# Multimeter.net
KiCad netlist of a schematic drawn in EAGLE
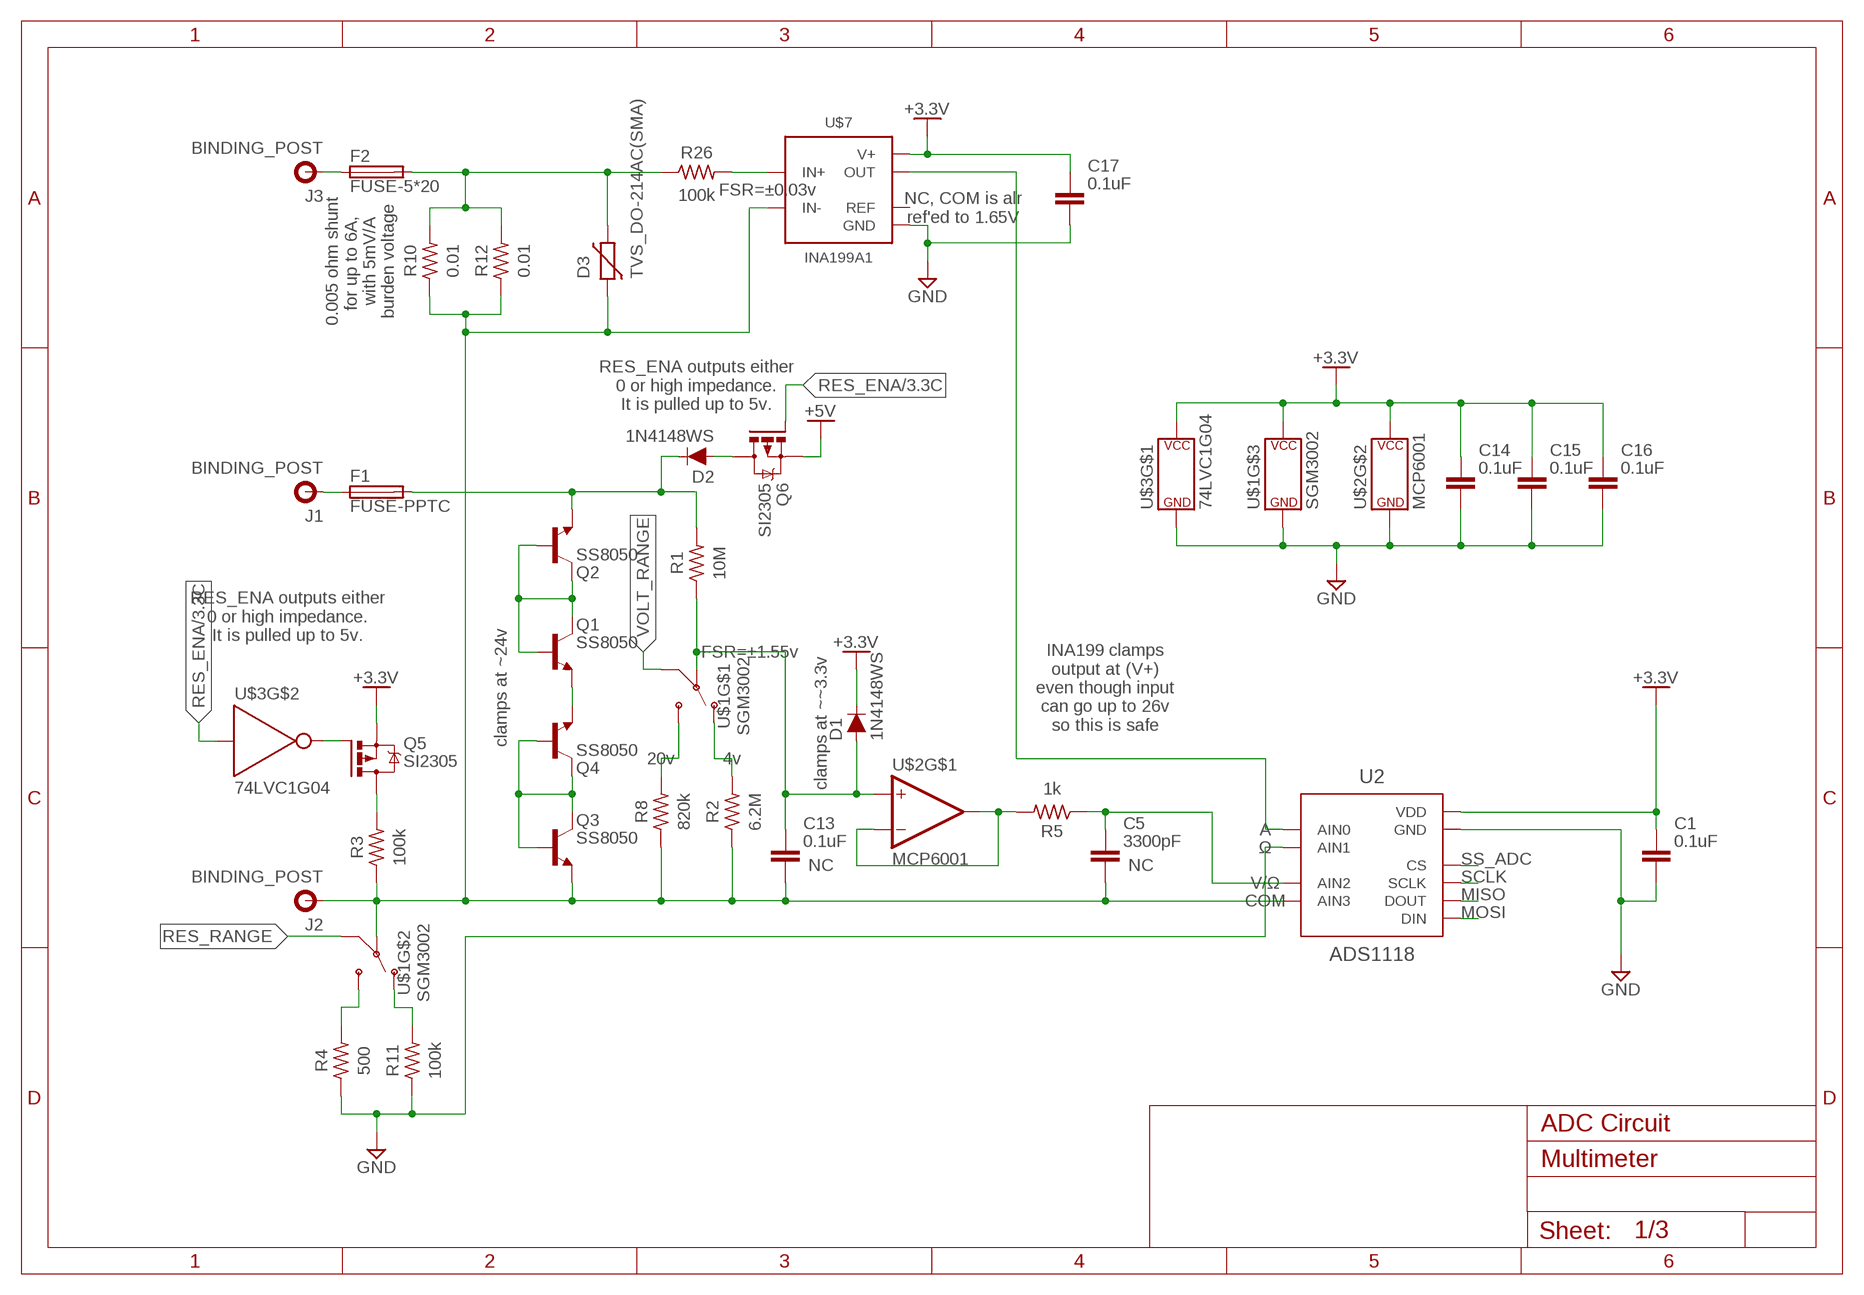
[diagram p0: schematic, sheet 1]
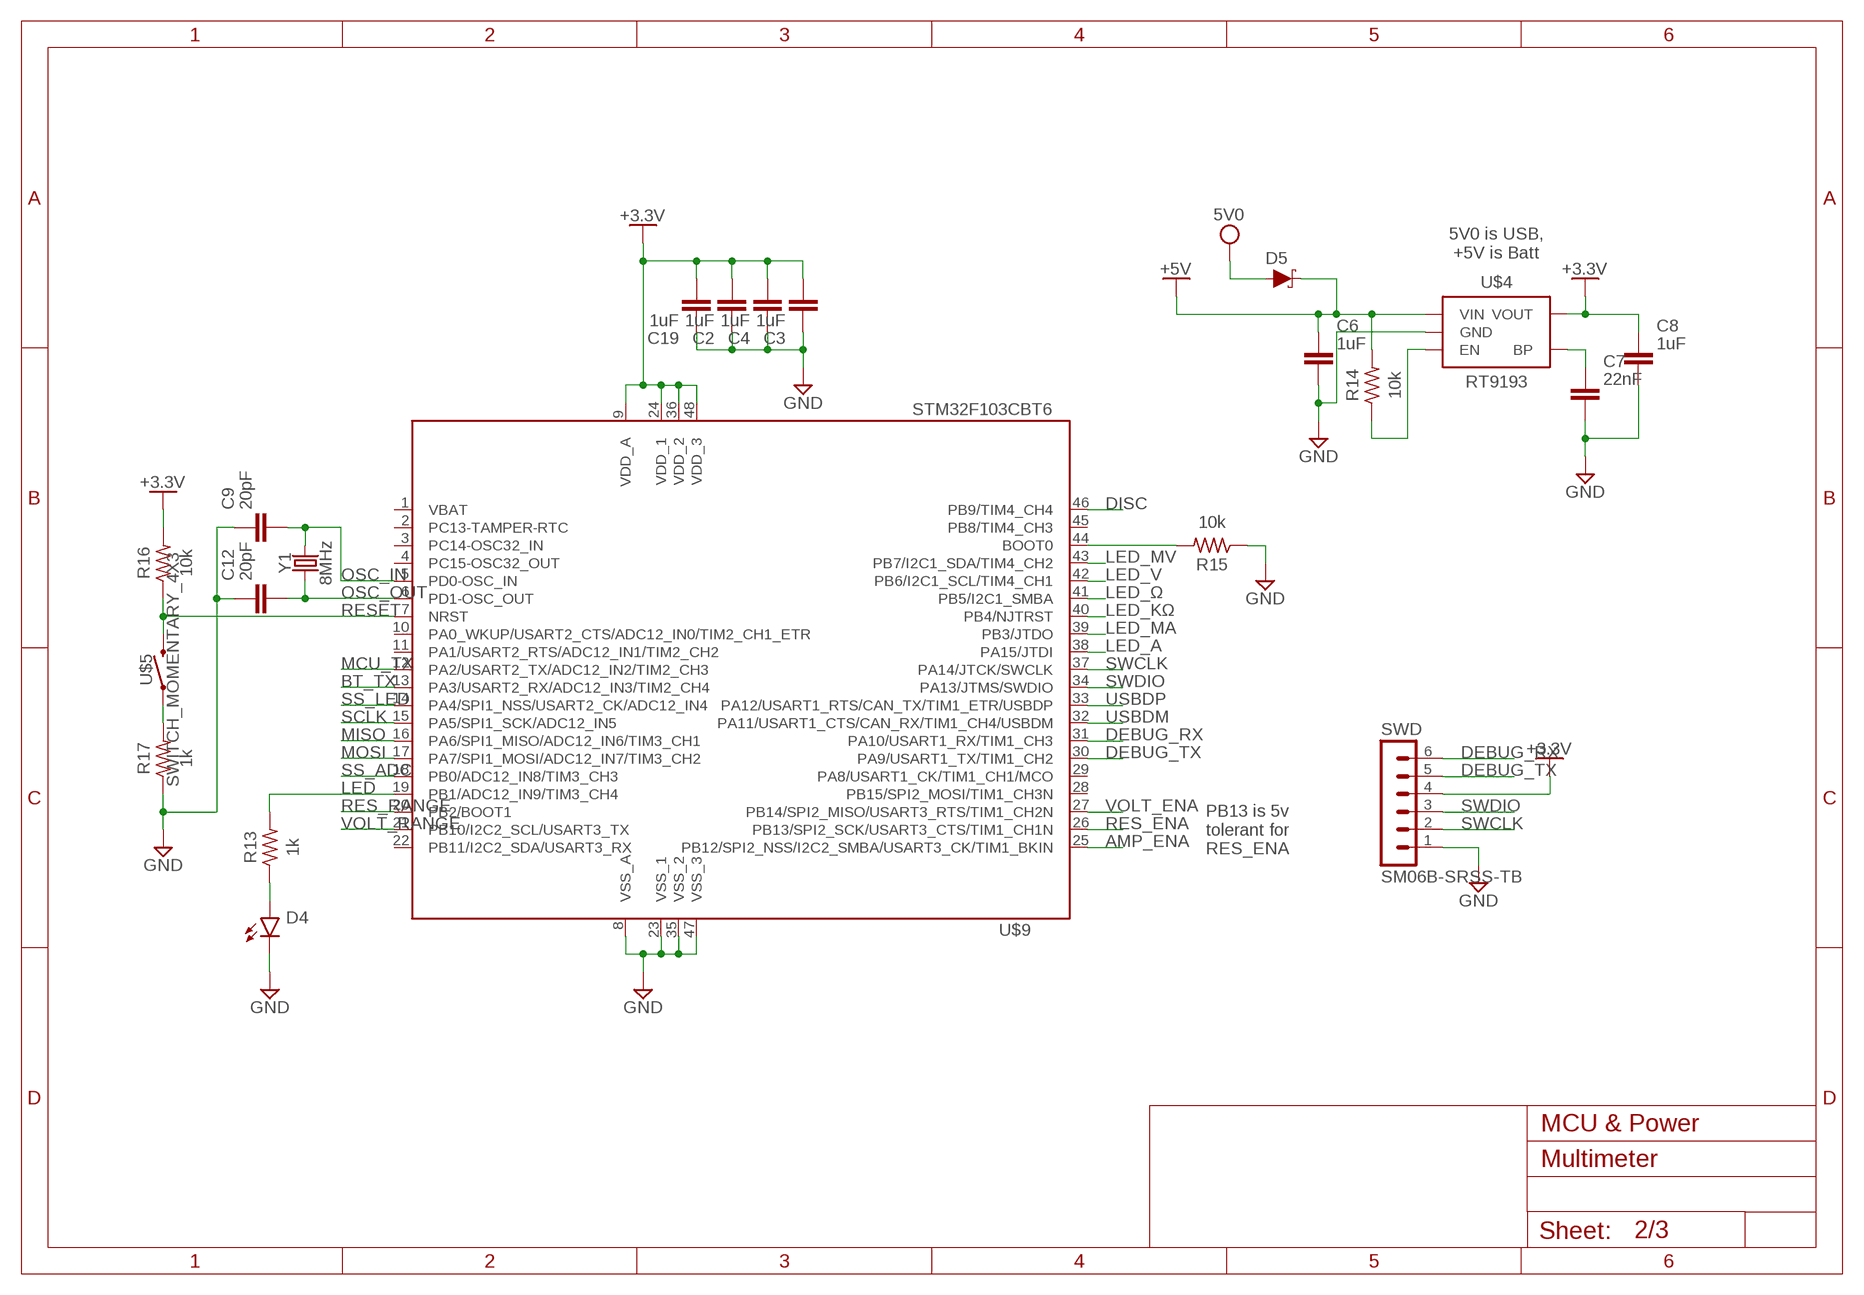
[diagram p1: schematic, sheet 2]
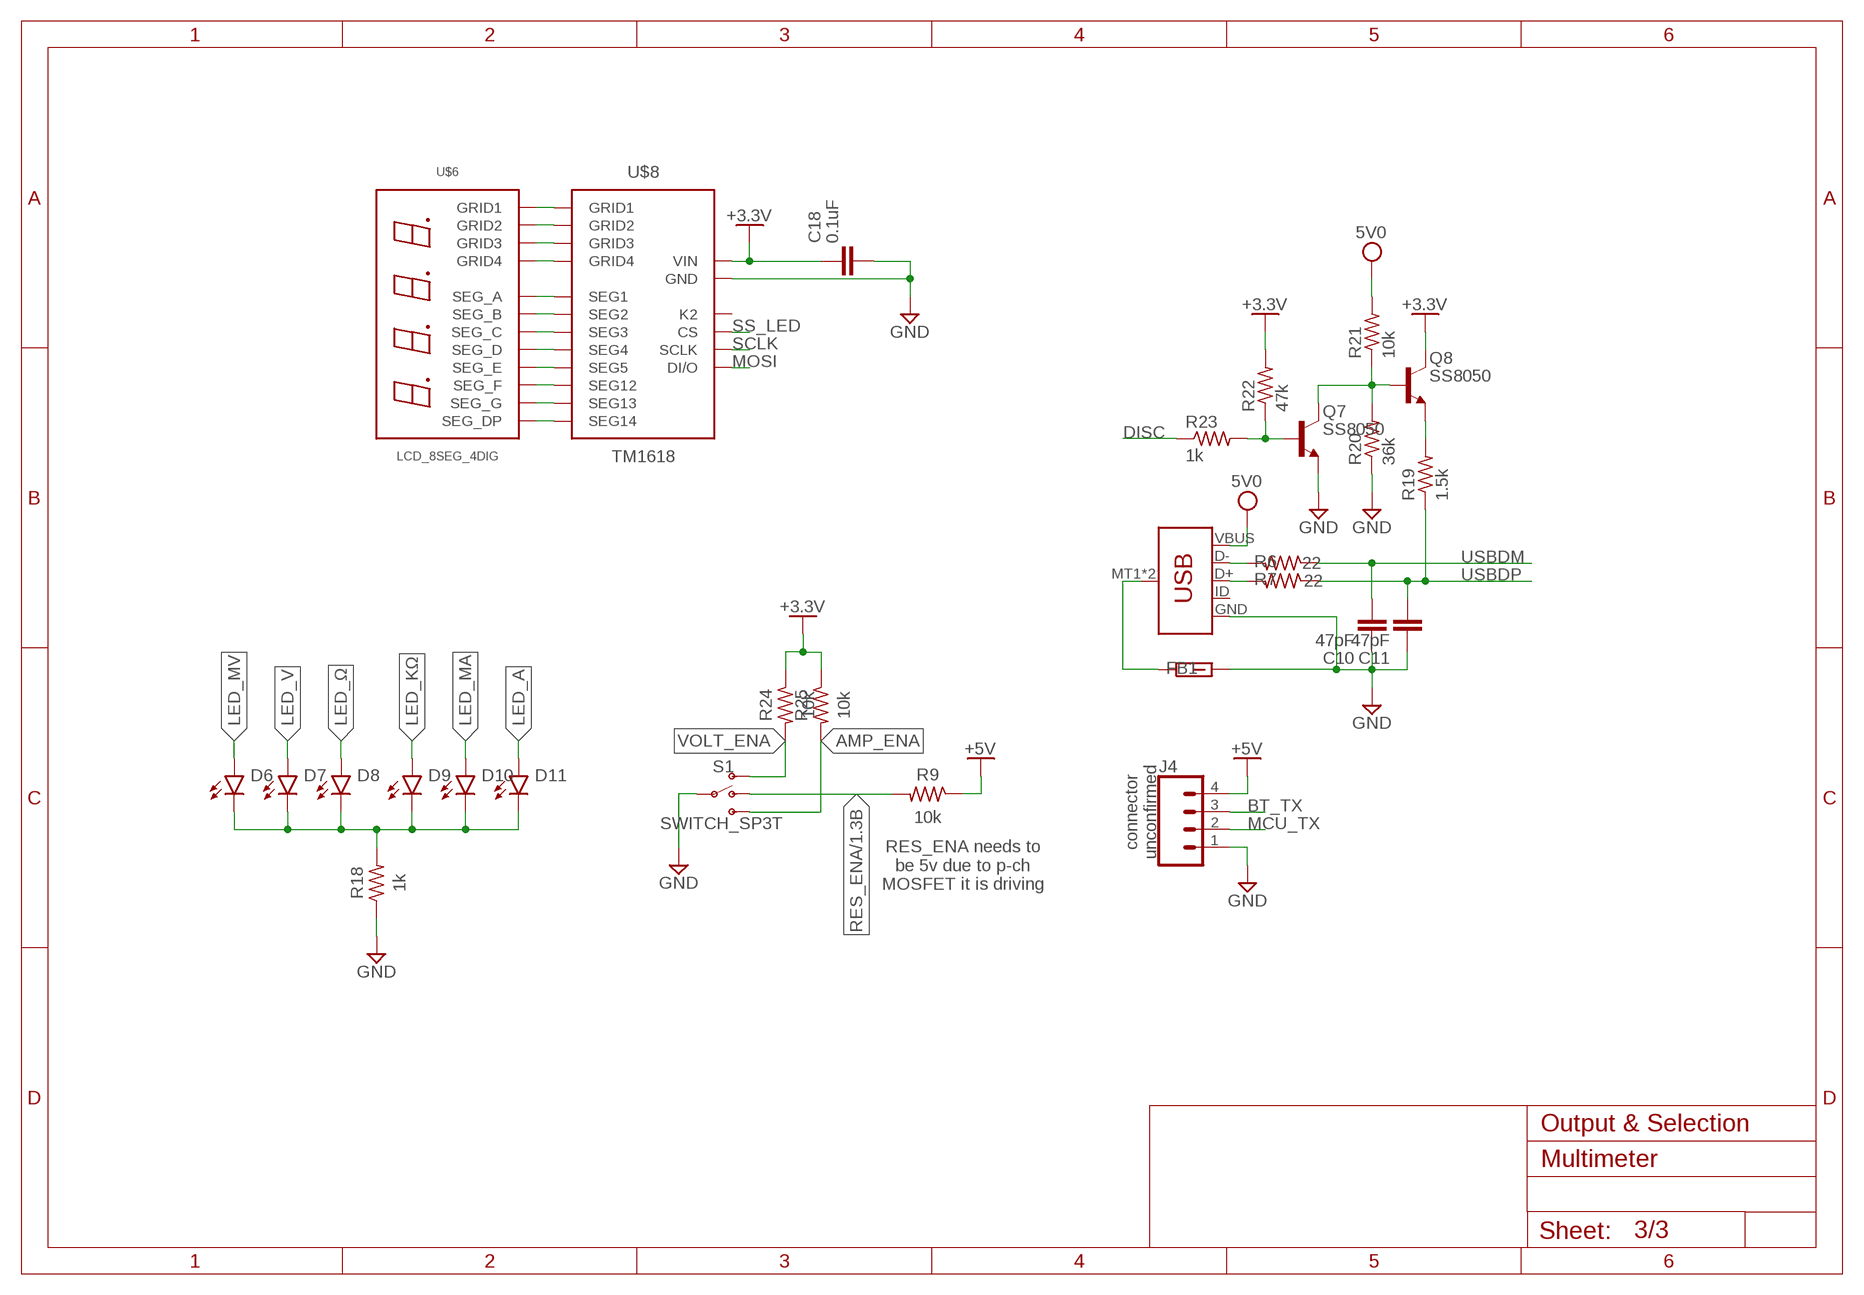
[diagram p2: schematic, sheet 3]

(export (version "E")
  (design (tool "Eeschema 10.0.6"))
  (components
    (comp (ref "C1")
      (value "0.1uF")
      (footprint "eagle-import:CAPC1608X85")
      (libsource (lib "eagle-import") (part "CCHIP-0603(1608-METRIC)_"))
    )
    (comp (ref "C5")
      (value "3300pF")
      (footprint "eagle-import:CAPC1608X85")
      (libsource (lib "eagle-import") (part "CCHIP-0603(1608-METRIC)_"))
    )
    (comp (ref "C13")
      (value "0.1uF")
      (footprint "eagle-import:CAPC1608X85")
      (libsource (lib "eagle-import") (part "CCHIP-0603(1608-METRIC)_"))
    )
    (comp (ref "C14")
      (value "0.1uF")
      (footprint "eagle-import:CAPC1608X85")
      (libsource (lib "eagle-import") (part "CCHIP-0603(1608-METRIC)_"))
    )
    (comp (ref "C15")
      (value "0.1uF")
      (footprint "eagle-import:CAPC1608X85")
      (libsource (lib "eagle-import") (part "CCHIP-0603(1608-METRIC)_"))
    )
    (comp (ref "C16")
      (value "0.1uF")
      (footprint "eagle-import:CAPC1608X85")
      (libsource (lib "eagle-import") (part "CCHIP-0603(1608-METRIC)_"))
    )
    (comp (ref "C17")
      (value "0.1uF")
      (footprint "eagle-import:CAPC1608X85")
      (libsource (lib "eagle-import") (part "CCHIP-0603(1608-METRIC)_"))
    )
    (comp (ref "D1")
      (value "1N4148WS")
      (footprint "eagle-import:SOD-323")
      (libsource (lib "eagle-import") (part "DIODE"))
    )
    (comp (ref "D2")
      (value "1N4148WS")
      (footprint "eagle-import:SOD-323")
      (libsource (lib "eagle-import") (part "DIODE"))
    )
    (comp (ref "D3")
      (value "TVS_DO-214AC(SMA)")
      (footprint "eagle-import:DIOM5226X290N")
      (libsource (lib "eagle-import") (part "TVSDO-214AC(SMA)_"))
    )
    (comp (ref "F1")
      (value "FUSE-PPTC")
      (footprint "eagle-import:FUSE-PPTC-TH")
      (libsource (lib "eagle-import") (part "FUSE-PPTC"))
    )
    (comp (ref "F2")
      (value "FUSE-5*20")
      (footprint "eagle-import:FUSEHOLDER__HD_")
      (libsource (lib "eagle-import") (part "FUSE-520"))
    )
    (comp (ref "J1")
      (value "BINDING_POST")
      (footprint "eagle-import:BINDING_POST")
      (libsource (lib "eagle-import") (part "BINDING_POST"))
    )
    (comp (ref "J2")
      (value "BINDING_POST")
      (footprint "eagle-import:BINDING_POST")
      (libsource (lib "eagle-import") (part "BINDING_POST"))
    )
    (comp (ref "J3")
      (value "BINDING_POST")
      (footprint "eagle-import:BINDING_POST")
      (libsource (lib "eagle-import") (part "BINDING_POST"))
    )
    (comp (ref "Q1")
      (value "SS8050")
      (footprint "eagle-import:SOT95P237X112-3N")
      (libsource (lib "eagle-import") (part "NPNSOT23_"))
    )
    (comp (ref "Q2")
      (value "SS8050")
      (footprint "eagle-import:SOT95P237X112-3N")
      (libsource (lib "eagle-import") (part "NPNSOT23_"))
    )
    (comp (ref "Q3")
      (value "SS8050")
      (footprint "eagle-import:SOT95P237X112-3N")
      (libsource (lib "eagle-import") (part "NPNSOT23_"))
    )
    (comp (ref "Q4")
      (value "SS8050")
      (footprint "eagle-import:SOT95P237X112-3N")
      (libsource (lib "eagle-import") (part "NPNSOT23_"))
    )
    (comp (ref "Q5")
      (value "SI2305")
      (footprint "eagle-import:SOT23")
      (libsource (lib "eagle-import") (part "PMOSFETSOT23_"))
    )
    (comp (ref "Q6")
      (value "SI2305")
      (footprint "eagle-import:SOT23")
      (libsource (lib "eagle-import") (part "PMOSFETSOT23_"))
    )
    (comp (ref "R1")
      (value "10M")
      (footprint "eagle-import:RESC1608X60")
      (libsource (lib "eagle-import") (part "R-USCHIP-0603(1608-METRIC)_"))
    )
    (comp (ref "R2")
      (value "6.2M")
      (footprint "eagle-import:RESC1608X60")
      (libsource (lib "eagle-import") (part "R-USCHIP-0603(1608-METRIC)_"))
    )
    (comp (ref "R3")
      (value "100k")
      (footprint "eagle-import:RESC1608X60")
      (libsource (lib "eagle-import") (part "R-USCHIP-0603(1608-METRIC)_"))
    )
    (comp (ref "R4")
      (value "500")
      (footprint "eagle-import:RESC1608X60")
      (libsource (lib "eagle-import") (part "R-USCHIP-0603(1608-METRIC)_"))
    )
    (comp (ref "R5")
      (value "1k")
      (footprint "eagle-import:RESC1608X60")
      (libsource (lib "eagle-import") (part "R-USCHIP-0603(1608-METRIC)_"))
    )
    (comp (ref "R8")
      (value "820k")
      (footprint "eagle-import:RESC1608X60")
      (libsource (lib "eagle-import") (part "R-USCHIP-0603(1608-METRIC)_"))
    )
    (comp (ref "R10")
      (value "0.01")
      (footprint "eagle-import:RESC6332X71")
      (libsource (lib "eagle-import") (part "R-USCHIP-2512(6332-METRIC)_"))
    )
    (comp (ref "R11")
      (value "100k")
      (footprint "eagle-import:RESC1608X60")
      (libsource (lib "eagle-import") (part "R-USCHIP-0603(1608-METRIC)_"))
    )
    (comp (ref "R12")
      (value "0.01")
      (footprint "eagle-import:RESC6332X71")
      (libsource (lib "eagle-import") (part "R-USCHIP-2512(6332-METRIC)_"))
    )
    (comp (ref "R26")
      (value "100k")
      (footprint "eagle-import:RESC1608X60")
      (libsource (lib "eagle-import") (part "R-USCHIP-0603(1608-METRIC)_"))
    )
    (comp (ref "U$1")
      (value "SGM3002")
      (footprint "eagle-import:MSOP10")
      (libsource (lib "eagle-import") (part "SGM3002"))
    )
    (comp (ref "U$2")
      (value "MCP6001")
      (footprint "eagle-import:SOT23-5")
      (libsource (lib "eagle-import") (part "MCP6001"))
    )
    (comp (ref "U$3")
      (value "74LVC1G04")
      (footprint "eagle-import:SOT23-5")
      (libsource (lib "eagle-import") (part "74LVC1G04"))
    )
    (comp (ref "U$7")
      (value "INA199A1")
      (footprint "eagle-import:SC70-6")
      (libsource (lib "eagle-import") (part "INA199"))
    )
    (comp (ref "U2")
      (value "ADS1118")
      (footprint "eagle-import:VSSOP10")
      (fields (field (name "MANUFACTURER") "Texas Instruments") (field (name "PARTNUMBER") "ADS1118IDGSR"))
      (libsource (lib "eagle-import") (part "ADS1118"))
    )
    (comp (ref "C10")
      (value "47pF")
      (footprint "eagle-import:CAPC1608X85")
      (libsource (lib "eagle-import") (part "CCHIP-0603(1608-METRIC)_"))
    )
    (comp (ref "C11")
      (value "47pF")
      (footprint "eagle-import:CAPC1608X85")
      (libsource (lib "eagle-import") (part "CCHIP-0603(1608-METRIC)_"))
    )
    (comp (ref "C18")
      (value "0.1uF")
      (footprint "eagle-import:CAPC1608X85")
      (libsource (lib "eagle-import") (part "CCHIP-0603(1608-METRIC)_"))
    )
    (comp (ref "D6")
      (value "LED_CHIP_BLUE-1608")
      (footprint "eagle-import:LEDC1608X39N_B")
      (libsource (lib "eagle-import") (part "LED_CHIPBLUE-1608_"))
    )
    (comp (ref "D7")
      (value "LED_CHIP_BLUE-1608")
      (footprint "eagle-import:LEDC1608X39N_B")
      (libsource (lib "eagle-import") (part "LED_CHIPBLUE-1608_"))
    )
    (comp (ref "D8")
      (value "LED_CHIP_BLUE-1608")
      (footprint "eagle-import:LEDC1608X39N_B")
      (libsource (lib "eagle-import") (part "LED_CHIPBLUE-1608_"))
    )
    (comp (ref "D9")
      (value "LED_CHIP_BLUE-1608")
      (footprint "eagle-import:LEDC1608X39N_B")
      (libsource (lib "eagle-import") (part "LED_CHIPBLUE-1608_"))
    )
    (comp (ref "D10")
      (value "LED_CHIP_BLUE-1608")
      (footprint "eagle-import:LEDC1608X39N_B")
      (libsource (lib "eagle-import") (part "LED_CHIPBLUE-1608_"))
    )
    (comp (ref "D11")
      (value "LED_CHIP_BLUE-1608")
      (footprint "eagle-import:LEDC1608X39N_B")
      (libsource (lib "eagle-import") (part "LED_CHIPBLUE-1608_"))
    )
    (comp (ref "FB1")
      (value "1k")
      (footprint "eagle-import:BEADC1608X95N")
      (libsource (lib "eagle-import") (part "FBCHIP-0603(1608-METRIC)"))
    )
    (comp (ref "J4")
      (value "CONN_04LOCK")
      (footprint "eagle-import:1X04_LOCK")
      (libsource (lib "eagle-import") (part "CONN_04LOCK"))
    )
    (comp (ref "Q7")
      (value "SS8050")
      (footprint "eagle-import:SOT95P237X112-3N")
      (libsource (lib "eagle-import") (part "NPNSOT23_"))
    )
    (comp (ref "Q8")
      (value "SS8050")
      (footprint "eagle-import:SOT95P237X112-3N")
      (libsource (lib "eagle-import") (part "NPNSOT23_"))
    )
    (comp (ref "R6")
      (value "22")
      (footprint "eagle-import:RESC1608X60")
      (libsource (lib "eagle-import") (part "R-USCHIP-0603(1608-METRIC)_"))
    )
    (comp (ref "R7")
      (value "22")
      (footprint "eagle-import:RESC1608X60")
      (libsource (lib "eagle-import") (part "R-USCHIP-0603(1608-METRIC)_"))
    )
    (comp (ref "R9")
      (value "10k")
      (footprint "eagle-import:RESC1608X60")
      (libsource (lib "eagle-import") (part "R-USCHIP-0603(1608-METRIC)_"))
    )
    (comp (ref "R18")
      (value "1k")
      (footprint "eagle-import:RESC1608X60")
      (libsource (lib "eagle-import") (part "R-USCHIP-0603(1608-METRIC)_"))
    )
    (comp (ref "R19")
      (value "1.5k")
      (footprint "eagle-import:RESC1608X60")
      (libsource (lib "eagle-import") (part "R-USCHIP-0603(1608-METRIC)_"))
    )
    (comp (ref "R20")
      (value "36k")
      (footprint "eagle-import:RESC1608X60")
      (libsource (lib "eagle-import") (part "R-USCHIP-0603(1608-METRIC)_"))
    )
    (comp (ref "R21")
      (value "10k")
      (footprint "eagle-import:RESC1608X60")
      (libsource (lib "eagle-import") (part "R-USCHIP-0603(1608-METRIC)_"))
    )
    (comp (ref "R22")
      (value "47k")
      (footprint "eagle-import:RESC1608X60")
      (libsource (lib "eagle-import") (part "R-USCHIP-0603(1608-METRIC)_"))
    )
    (comp (ref "R23")
      (value "1k")
      (footprint "eagle-import:RESC1608X60")
      (libsource (lib "eagle-import") (part "R-USCHIP-0603(1608-METRIC)_"))
    )
    (comp (ref "R24")
      (value "10k")
      (footprint "eagle-import:RESC1608X60")
      (libsource (lib "eagle-import") (part "R-USCHIP-0603(1608-METRIC)_"))
    )
    (comp (ref "R25")
      (value "10k")
      (footprint "eagle-import:RESC1608X60")
      (libsource (lib "eagle-import") (part "R-USCHIP-0603(1608-METRIC)_"))
    )
    (comp (ref "S1")
      (value "SWITCH_SP3T")
      (footprint "eagle-import:SWITCH_SP3T")
      (libsource (lib "eagle-import") (part "SWITCH_SP3T"))
    )
    (comp (ref "U$6")
      (value "LCD_8SEG_4DIG")
      (footprint "eagle-import:LCD_8SEG_4DIG_0.4IN")
      (libsource (lib "eagle-import") (part "LCD_8SEG_4DIG"))
    )
    (comp (ref "U$8")
      (value "TM1618")
      (footprint "eagle-import:SOP-18")
      (libsource (lib "eagle-import") (part "TM1618"))
    )
    (comp (ref "X1")
      (value "USB-MINIB")
      (footprint "eagle-import:USB-MICROB-CLEANED")
      (libsource (lib "eagle-import") (part "USB_MICRO-B"))
    )
    (comp (ref "C2")
      (value "1uF")
      (footprint "eagle-import:CAPC1608X85")
      (libsource (lib "eagle-import") (part "CCHIP-0603(1608-METRIC)_"))
    )
    (comp (ref "C3")
      (value "1uF")
      (footprint "eagle-import:CAPC1608X85")
      (libsource (lib "eagle-import") (part "CCHIP-0603(1608-METRIC)_"))
    )
    (comp (ref "C4")
      (value "1uF")
      (footprint "eagle-import:CAPC1608X85")
      (libsource (lib "eagle-import") (part "CCHIP-0603(1608-METRIC)_"))
    )
    (comp (ref "C6")
      (value "1uF")
      (footprint "eagle-import:CAPC1608X85")
      (libsource (lib "eagle-import") (part "CCHIP-0603(1608-METRIC)_"))
    )
    (comp (ref "C7")
      (value "22nF")
      (footprint "eagle-import:CAPC1608X85")
      (libsource (lib "eagle-import") (part "CCHIP-0603(1608-METRIC)_"))
    )
    (comp (ref "C8")
      (value "1uF")
      (footprint "eagle-import:CAPC1608X85")
      (libsource (lib "eagle-import") (part "CCHIP-0603(1608-METRIC)_"))
    )
    (comp (ref "C9")
      (value "20pF")
      (footprint "eagle-import:CAPC1608X85")
      (libsource (lib "eagle-import") (part "CCHIP-0603(1608-METRIC)_"))
    )
    (comp (ref "C12")
      (value "20pF")
      (footprint "eagle-import:CAPC1608X85")
      (libsource (lib "eagle-import") (part "CCHIP-0603(1608-METRIC)_"))
    )
    (comp (ref "C19")
      (value "1uF")
      (footprint "eagle-import:CAPC1608X85")
      (libsource (lib "eagle-import") (part "CCHIP-0603(1608-METRIC)_"))
    )
    (comp (ref "D4")
      (value "LED_CHIP_BLUE-1608")
      (footprint "eagle-import:LEDC1608X39N_B")
      (libsource (lib "eagle-import") (part "LED_CHIPBLUE-1608_"))
    )
    (comp (ref "D5")
      (value "DIODE-SCHOTTKY")
      (footprint "eagle-import:SMA-DIODE")
      (libsource (lib "eagle-import") (part "DIODE-SCHOTTKY"))
    )
    (comp (ref "R13")
      (value "1k")
      (footprint "eagle-import:RESC1608X60")
      (libsource (lib "eagle-import") (part "R-USCHIP-0603(1608-METRIC)_"))
    )
    (comp (ref "R14")
      (value "10k")
      (footprint "eagle-import:RESC1608X60")
      (libsource (lib "eagle-import") (part "R-USCHIP-0603(1608-METRIC)_"))
    )
    (comp (ref "R15")
      (value "10k")
      (footprint "eagle-import:RESC1608X60")
      (libsource (lib "eagle-import") (part "R-USCHIP-0603(1608-METRIC)_"))
    )
    (comp (ref "R16")
      (value "10k")
      (footprint "eagle-import:RESC1608X60")
      (libsource (lib "eagle-import") (part "R-USCHIP-0603(1608-METRIC)_"))
    )
    (comp (ref "R17")
      (value "1k")
      (footprint "eagle-import:RESC1608X60")
      (libsource (lib "eagle-import") (part "R-USCHIP-0603(1608-METRIC)_"))
    )
    (comp (ref "SWD")
      (value "SM06B-SRSS-TB")
      (footprint "eagle-import:SM06B-SRSS-TB")
      (libsource (lib "eagle-import") (part "SM06B-SRSS-TB"))
    )
    (comp (ref "U$4")
      (value "RT9193")
      (footprint "eagle-import:SOT23-5")
      (libsource (lib "eagle-import") (part "RT9193"))
    )
    (comp (ref "U$5")
      (value "SWITCH_MOMENTARY_4X3")
      (footprint "eagle-import:MOMENTARY_SWITCH_4X3")
      (libsource (lib "eagle-import") (part "SWITCH_MOMENTARY_4X3"))
    )
    (comp (ref "U$9")
      (value "STM32F103CBT6")
      (footprint "eagle-import:LQFP48")
      (libsource (lib "eagle-import") (part "STM32F103CBT6"))
    )
    (comp (ref "Y1")
      (value "8MHz")
      (footprint "eagle-import:CRYSTAL-SMD-5X3.2-2PAD")
      (libsource (lib "eagle-import") (part "CRYSTAL_5032"))
    )
  )
  (nets
    (net (code "1") (name "+3.3V") (class "Default")
      (node (ref "C1") (pin "1") (pinfunction "1_1") (pintype "passive"))
      (node (ref "C14") (pin "1") (pinfunction "1_1") (pintype "passive"))
      (node (ref "C15") (pin "1") (pinfunction "1_1") (pintype "passive"))
      (node (ref "C16") (pin "1") (pinfunction "1_1") (pintype "passive"))
      (node (ref "C17") (pin "1") (pinfunction "1_1") (pintype "passive"))
      (node (ref "C18") (pin "1") (pinfunction "1_1") (pintype "passive"))
      (node (ref "C19") (pin "2") (pinfunction "2_2") (pintype "passive"))
      (node (ref "C2") (pin "2") (pinfunction "2_2") (pintype "passive"))
      (node (ref "C3") (pin "2") (pinfunction "2_2") (pintype "passive"))
      (node (ref "C4") (pin "2") (pinfunction "2_2") (pintype "passive"))
      (node (ref "C8") (pin "1") (pinfunction "1_1") (pintype "passive"))
      (node (ref "D1") (pin "C") (pinfunction "C_C") (pintype "passive"))
      (node (ref "Q5") (pin "2") (pinfunction "S_2") (pintype "passive"))
      (node (ref "Q8") (pin "3") (pinfunction "C_3") (pintype "passive"))
      (node (ref "R16") (pin "2") (pinfunction "2_2") (pintype "passive"))
      (node (ref "R22") (pin "2") (pinfunction "2_2") (pintype "passive"))
      (node (ref "R24") (pin "1") (pinfunction "1_1") (pintype "passive"))
      (node (ref "R25") (pin "1") (pinfunction "1_1") (pintype "passive"))
      (node (ref "SWD") (pin "4") (pinfunction "4_4") (pintype "passive"))
      (node (ref "U$1") (pin "8") (pinfunction "P$V+_8") (pintype "bidirectional"))
      (node (ref "U$2") (pin "5") (pinfunction "P$V+_5") (pintype "bidirectional"))
      (node (ref "U$3") (pin "5") (pinfunction "P$V+_5") (pintype "bidirectional"))
      (node (ref "U$4") (pin "5") (pinfunction "VOUT_5") (pintype "bidirectional"))
      (node (ref "U$7") (pin "3") (pinfunction "V+_3") (pintype "bidirectional"))
      (node (ref "U$8") (pin "P5") (pinfunction "VIN_P5") (pintype "bidirectional"))
      (node (ref "U$9") (pin "24") (pinfunction "VDD_1_24") (pintype "power_in"))
      (node (ref "U$9") (pin "36") (pinfunction "VDD_2_36") (pintype "power_in"))
      (node (ref "U$9") (pin "48") (pinfunction "VDD_3_48") (pintype "power_in"))
      (node (ref "U$9") (pin "9") (pinfunction "VDD_A_9") (pintype "power_in"))
      (node (ref "U2") (pin "8") (pinfunction "VDD_8") (pintype "power_in"))
    )
    (net (code "2") (name "+5V") (class "Default")
      (node (ref "C6") (pin "1") (pinfunction "1_1") (pintype "passive"))
      (node (ref "D5") (pin "C") (pinfunction "C_C") (pintype "passive"))
      (node (ref "J4") (pin "4") (pinfunction "4_4") (pintype "passive"))
      (node (ref "Q6") (pin "2") (pinfunction "S_2") (pintype "passive"))
      (node (ref "R14") (pin "2") (pinfunction "2_2") (pintype "passive"))
      (node (ref "R9") (pin "1") (pinfunction "1_1") (pintype "passive"))
      (node (ref "U$4") (pin "1") (pinfunction "VIN_1") (pintype "bidirectional"))
    )
    (net (code "3") (name "5V0") (class "Default")
      (node (ref "D5") (pin "A") (pinfunction "A_A") (pintype "passive"))
      (node (ref "R21") (pin "2") (pinfunction "2_2") (pintype "passive"))
      (node (ref "X1") (pin "VBUS") (pinfunction "VBUS_VBUS") (pintype "power_in"))
    )
    (net (code "4") (name "AMP_ENA") (class "Default")
      (node (ref "R25") (pin "2") (pinfunction "2_2") (pintype "passive"))
      (node (ref "S1") (pin "4") (pinfunction "4_4") (pintype "passive"))
      (node (ref "U$9") (pin "25") (pinfunction "PB12/SPI2_NSS/I2C2_SMBA/USART3_CK/TIM1_BKIN_25") (pintype "input"))
    )
    (net (code "5") (name "BT_TX") (class "Default")
      (node (ref "J4") (pin "3") (pinfunction "3_3") (pintype "passive"))
      (node (ref "U$9") (pin "13") (pinfunction "PA3/USART2_RX/ADC12_IN3/TIM2_CH4_13") (pintype "bidirectional"))
    )
    (net (code "6") (name "DEBUG_RX") (class "Default")
      (node (ref "SWD") (pin "6") (pinfunction "6_6") (pintype "passive"))
      (node (ref "U$9") (pin "31") (pinfunction "PA10/USART1_RX/TIM1_CH3_31") (pintype "bidirectional"))
    )
    (net (code "7") (name "DEBUG_TX") (class "Default")
      (node (ref "SWD") (pin "5") (pinfunction "5_5") (pintype "passive"))
      (node (ref "U$9") (pin "30") (pinfunction "PA9/USART1_TX/TIM1_CH2_30") (pintype "input"))
    )
    (net (code "8") (name "DISC") (class "Default")
      (node (ref "R23") (pin "1") (pinfunction "1_1") (pintype "passive"))
      (node (ref "U$9") (pin "46") (pinfunction "PB9/TIM4_CH4_46") (pintype "input"))
    )
    (net (code "9") (name "GND") (class "Default")
      (node (ref "C1") (pin "2") (pinfunction "2_2") (pintype "passive"))
      (node (ref "C10") (pin "1") (pinfunction "1_1") (pintype "passive"))
      (node (ref "C11") (pin "1") (pinfunction "1_1") (pintype "passive"))
      (node (ref "C12") (pin "1") (pinfunction "1_1") (pintype "passive"))
      (node (ref "C14") (pin "2") (pinfunction "2_2") (pintype "passive"))
      (node (ref "C15") (pin "2") (pinfunction "2_2") (pintype "passive"))
      (node (ref "C16") (pin "2") (pinfunction "2_2") (pintype "passive"))
      (node (ref "C17") (pin "2") (pinfunction "2_2") (pintype "passive"))
      (node (ref "C18") (pin "2") (pinfunction "2_2") (pintype "passive"))
      (node (ref "C19") (pin "1") (pinfunction "1_1") (pintype "passive"))
      (node (ref "C2") (pin "1") (pinfunction "1_1") (pintype "passive"))
      (node (ref "C3") (pin "1") (pinfunction "1_1") (pintype "passive"))
      (node (ref "C4") (pin "1") (pinfunction "1_1") (pintype "passive"))
      (node (ref "C6") (pin "2") (pinfunction "2_2") (pintype "passive"))
      (node (ref "C7") (pin "2") (pinfunction "2_2") (pintype "passive"))
      (node (ref "C8") (pin "2") (pinfunction "2_2") (pintype "passive"))
      (node (ref "C9") (pin "1") (pinfunction "1_1") (pintype "passive"))
      (node (ref "D4") (pin "2") (pinfunction "C_2") (pintype "passive"))
      (node (ref "FB1") (pin "2") (pinfunction "2_2") (pintype "passive"))
      (node (ref "J4") (pin "1") (pinfunction "1_1") (pintype "passive"))
      (node (ref "Q7") (pin "1") (pinfunction "E_1") (pintype "passive"))
      (node (ref "R11") (pin "1") (pinfunction "1_1") (pintype "passive"))
      (node (ref "R15") (pin "1") (pinfunction "1_1") (pintype "passive"))
      (node (ref "R17") (pin "1") (pinfunction "1_1") (pintype "passive"))
      (node (ref "R18") (pin "1") (pinfunction "1_1") (pintype "passive"))
      (node (ref "R20") (pin "1") (pinfunction "1_1") (pintype "passive"))
      (node (ref "R4") (pin "1") (pinfunction "1_1") (pintype "passive"))
      (node (ref "S1") (pin "3") (pinfunction "3_3") (pintype "passive"))
      (node (ref "SWD") (pin "1") (pinfunction "1_1") (pintype "passive"))
      (node (ref "U$1") (pin "3") (pinfunction "P$V-_3") (pintype "bidirectional"))
      (node (ref "U$2") (pin "2") (pinfunction "P$V-_2") (pintype "bidirectional"))
      (node (ref "U$3") (pin "3") (pinfunction "P$V-_3") (pintype "bidirectional"))
      (node (ref "U$4") (pin "2") (pinfunction "GND_2") (pintype "bidirectional"))
      (node (ref "U$7") (pin "2") (pinfunction "GND_2") (pintype "bidirectional"))
      (node (ref "U$8") (pin "P16") (pinfunction "GND_P16") (pintype "bidirectional"))
      (node (ref "U$9") (pin "23") (pinfunction "VSS_1_23") (pintype "power_in"))
      (node (ref "U$9") (pin "35") (pinfunction "VSS_2_35") (pintype "power_in"))
      (node (ref "U$9") (pin "47") (pinfunction "VSS_3_47") (pintype "power_in"))
      (node (ref "U$9") (pin "8") (pinfunction "VSS_A_8") (pintype "power_in"))
      (node (ref "U2") (pin "3") (pinfunction "GND_3") (pintype "power_in"))
      (node (ref "U2") (pin "5") (pinfunction "AIN1_5") (pintype "input"))
      (node (ref "X1") (pin "GND") (pinfunction "GND_GND") (pintype "power_in"))
    )
    (net (code "10") (name "LED") (class "Default")
      (node (ref "R13") (pin "2") (pinfunction "2_2") (pintype "passive"))
      (node (ref "U$9") (pin "19") (pinfunction "PB1/ADC12_IN9/TIM3_CH4_19") (pintype "bidirectional"))
    )
    (net (code "11") (name "LED_A") (class "Default")
      (node (ref "D11") (pin "1") (pinfunction "A_1") (pintype "passive"))
      (node (ref "U$9") (pin "38") (pinfunction "PA15/JTDI_38") (pintype "bidirectional"))
    )
    (net (code "12") (name "LED_KΩ") (class "Default")
      (node (ref "D9") (pin "1") (pinfunction "A_1") (pintype "passive"))
      (node (ref "U$9") (pin "40") (pinfunction "PB4/NJTRST_40") (pintype "bidirectional"))
    )
    (net (code "13") (name "LED_MA") (class "Default")
      (node (ref "D10") (pin "1") (pinfunction "A_1") (pintype "passive"))
      (node (ref "U$9") (pin "39") (pinfunction "PB3/JTDO_39") (pintype "bidirectional"))
    )
    (net (code "14") (name "LED_MV") (class "Default")
      (node (ref "D6") (pin "1") (pinfunction "A_1") (pintype "passive"))
      (node (ref "U$9") (pin "43") (pinfunction "PB7/I2C1_SDA/TIM4_CH2_43") (pintype "bidirectional"))
    )
    (net (code "15") (name "LED_V") (class "Default")
      (node (ref "D7") (pin "1") (pinfunction "A_1") (pintype "passive"))
      (node (ref "U$9") (pin "42") (pinfunction "PB6/I2C1_SCL/TIM4_CH1_42") (pintype "input"))
    )
    (net (code "16") (name "LED_Ω") (class "Default")
      (node (ref "D8") (pin "1") (pinfunction "A_1") (pintype "passive"))
      (node (ref "U$9") (pin "41") (pinfunction "PB5/I2C1_SMBA_41") (pintype "input"))
    )
    (net (code "17") (name "MCU_TX") (class "Default")
      (node (ref "J4") (pin "2") (pinfunction "2_2") (pintype "passive"))
      (node (ref "U$9") (pin "12") (pinfunction "PA2/USART2_TX/ADC12_IN2/TIM2_CH3_12") (pintype "bidirectional"))
    )
    (net (code "18") (name "MISO") (class "Default")
      (node (ref "U$9") (pin "16") (pinfunction "PA6/SPI1_MISO/ADC12_IN6/TIM3_CH1_16") (pintype "bidirectional"))
      (node (ref "U2") (pin "9") (pinfunction "DOUT_9") (pintype "output"))
    )
    (net (code "19") (name "MOSI") (class "Default")
      (node (ref "U$8") (pin "P1") (pinfunction "DI/O_P1") (pintype "bidirectional"))
      (node (ref "U$9") (pin "17") (pinfunction "PA7/SPI1_MOSI/ADC12_IN7/TIM3_CH2_17") (pintype "bidirectional"))
      (node (ref "U2") (pin "10") (pinfunction "DIN_10") (pintype "input"))
    )
    (net (code "20") (name "Net-(D4-A)") (class "Default")
      (node (ref "D4") (pin "1") (pinfunction "A_1") (pintype "passive"))
      (node (ref "R13") (pin "1") (pinfunction "1_1") (pintype "passive"))
    )
    (net (code "21") (name "Net-(D10-C)") (class "Default")
      (node (ref "D10") (pin "2") (pinfunction "C_2") (pintype "passive"))
      (node (ref "D11") (pin "2") (pinfunction "C_2") (pintype "passive"))
      (node (ref "D6") (pin "2") (pinfunction "C_2") (pintype "passive"))
      (node (ref "D7") (pin "2") (pinfunction "C_2") (pintype "passive"))
      (node (ref "D8") (pin "2") (pinfunction "C_2") (pintype "passive"))
      (node (ref "D9") (pin "2") (pinfunction "C_2") (pintype "passive"))
      (node (ref "R18") (pin "2") (pinfunction "2_2") (pintype "passive"))
    )
    (net (code "22") (name "Net-(F1-1)") (class "Default")
      (node (ref "F1") (pin "P$1") (pinfunction "1_P$1") (pintype "passive"))
      (node (ref "J1") (pin "P$1") (pinfunction "P$1_P$1") (pintype "bidirectional"))
    )
    (net (code "23") (name "Net-(F1-2)") (class "Default")
      (node (ref "D2") (pin "C") (pinfunction "C_C") (pintype "passive"))
      (node (ref "F1") (pin "P$2") (pinfunction "2_P$2") (pintype "passive"))
      (node (ref "Q2") (pin "1") (pinfunction "E_1") (pintype "passive"))
      (node (ref "R1") (pin "2") (pinfunction "2_2") (pintype "passive"))
    )
    (net (code "24") (name "Net-(F2-1)") (class "Default")
      (node (ref "F2") (pin "P$1") (pinfunction "1_P$1") (pintype "passive"))
      (node (ref "J3") (pin "P$1") (pinfunction "P$1_P$1") (pintype "bidirectional"))
    )
    (net (code "25") (name "Net-(F2-2)") (class "Default")
      (node (ref "D3") (pin "2") (pinfunction "2_2") (pintype "passive"))
      (node (ref "F2") (pin "P$2") (pinfunction "2_P$2") (pintype "passive"))
      (node (ref "R10") (pin "2") (pinfunction "2_2") (pintype "passive"))
      (node (ref "R12") (pin "2") (pinfunction "2_2") (pintype "passive"))
      (node (ref "R26") (pin "1") (pinfunction "1_1") (pintype "passive"))
    )
    (net (code "26") (name "Net-(FB1-Pad1)") (class "Default")
      (node (ref "FB1") (pin "1") (pinfunction "1_1") (pintype "passive"))
      (node (ref "X1") (pin "MT1") (pinfunction "SHIELD_MT1") (pintype "bidirectional"))
      (node (ref "X1") (pin "MT2") (pinfunction "SHIELD_MT2") (pintype "bidirectional"))
    )
    (net (code "27") (name "Net-(Q1-B)") (class "Default")
      (node (ref "Q1") (pin "2") (pinfunction "B_2") (pintype "passive"))
      (node (ref "Q1") (pin "3") (pinfunction "C_3") (pintype "passive"))
      (node (ref "Q2") (pin "2") (pinfunction "B_2") (pintype "passive"))
      (node (ref "Q2") (pin "3") (pinfunction "C_3") (pintype "passive"))
    )
    (net (code "28") (name "Net-(Q1-E)") (class "Default")
      (node (ref "Q1") (pin "1") (pinfunction "E_1") (pintype "passive"))
      (node (ref "Q4") (pin "1") (pinfunction "E_1") (pintype "passive"))
    )
    (net (code "29") (name "Net-(Q3-B)") (class "Default")
      (node (ref "Q3") (pin "2") (pinfunction "B_2") (pintype "passive"))
      (node (ref "Q3") (pin "3") (pinfunction "C_3") (pintype "passive"))
      (node (ref "Q4") (pin "2") (pinfunction "B_2") (pintype "passive"))
      (node (ref "Q4") (pin "3") (pinfunction "C_3") (pintype "passive"))
    )
    (net (code "30") (name "Net-(Q3-E)") (class "Default")
      (node (ref "C13") (pin "2") (pinfunction "2_2") (pintype "passive"))
      (node (ref "C5") (pin "2") (pinfunction "2_2") (pintype "passive"))
      (node (ref "D3") (pin "1") (pinfunction "1_1") (pintype "passive"))
      (node (ref "J2") (pin "P$1") (pinfunction "P$1_P$1") (pintype "bidirectional"))
      (node (ref "Q3") (pin "1") (pinfunction "E_1") (pintype "passive"))
      (node (ref "R10") (pin "1") (pinfunction "1_1") (pintype "passive"))
      (node (ref "R12") (pin "1") (pinfunction "1_1") (pintype "passive"))
      (node (ref "R2") (pin "1") (pinfunction "1_1") (pintype "passive"))
      (node (ref "R3") (pin "1") (pinfunction "1_1") (pintype "passive"))
      (node (ref "R8") (pin "1") (pinfunction "1_1") (pintype "passive"))
      (node (ref "U$1") (pin "6") (pinfunction "COM_6") (pintype "passive"))
      (node (ref "U$7") (pin "5") (pinfunction "IN-_5") (pintype "bidirectional"))
      (node (ref "U2") (pin "7") (pinfunction "AIN3_7") (pintype "input"))
    )
    (net (code "31") (name "Net-(Q5-D)") (class "Default")
      (node (ref "Q5") (pin "3") (pinfunction "D_3") (pintype "passive"))
      (node (ref "R3") (pin "2") (pinfunction "2_2") (pintype "passive"))
    )
    (net (code "32") (name "Net-(Q5-G)") (class "Default")
      (node (ref "Q5") (pin "1") (pinfunction "G_1") (pintype "passive"))
      (node (ref "U$3") (pin "4") (pinfunction "Y_4") (pintype "output"))
    )
    (net (code "33") (name "Net-(Q6-D)") (class "Default")
      (node (ref "D2") (pin "A") (pinfunction "A_A") (pintype "passive"))
      (node (ref "Q6") (pin "3") (pinfunction "D_3") (pintype "passive"))
    )
    (net (code "34") (name "Net-(Q7-B)") (class "Default")
      (node (ref "Q7") (pin "2") (pinfunction "B_2") (pintype "passive"))
      (node (ref "R22") (pin "1") (pinfunction "1_1") (pintype "passive"))
      (node (ref "R23") (pin "2") (pinfunction "2_2") (pintype "passive"))
    )
    (net (code "35") (name "Net-(Q7-C)") (class "Default")
      (node (ref "Q7") (pin "3") (pinfunction "C_3") (pintype "passive"))
      (node (ref "Q8") (pin "2") (pinfunction "B_2") (pintype "passive"))
      (node (ref "R20") (pin "2") (pinfunction "2_2") (pintype "passive"))
      (node (ref "R21") (pin "1") (pinfunction "1_1") (pintype "passive"))
    )
    (net (code "36") (name "Net-(Q8-E)") (class "Default")
      (node (ref "Q8") (pin "1") (pinfunction "E_1") (pintype "passive"))
      (node (ref "R19") (pin "2") (pinfunction "2_2") (pintype "passive"))
    )
    (net (code "37") (name "Net-(R6-Pad2)") (class "Default")
      (node (ref "R6") (pin "2") (pinfunction "2_2") (pintype "passive"))
      (node (ref "X1") (pin "D-") (pinfunction "D-_D-") (pintype "bidirectional"))
    )
    (net (code "38") (name "Net-(R7-Pad2)") (class "Default")
      (node (ref "R7") (pin "2") (pinfunction "2_2") (pintype "passive"))
      (node (ref "X1") (pin "D+") (pinfunction "D+_D+") (pintype "bidirectional"))
    )
    (net (code "39") (name "Net-(U$1A-COM)") (class "Default")
      (node (ref "C13") (pin "1") (pinfunction "1_1") (pintype "passive"))
      (node (ref "D1") (pin "A") (pinfunction "A_A") (pintype "passive"))
      (node (ref "R1") (pin "1") (pinfunction "1_1") (pintype "passive"))
      (node (ref "U$1") (pin "10") (pinfunction "COM_10") (pintype "passive"))
      (node (ref "U$2") (pin "3") (pinfunction "+IN_3") (pintype "input"))
    )
    (net (code "40") (name "Net-(U$1A-NC)") (class "Default")
      (node (ref "R2") (pin "2") (pinfunction "2_2") (pintype "passive"))
      (node (ref "U$1") (pin "9") (pinfunction "NC_9") (pintype "passive"))
    )
    (net (code "41") (name "Net-(U$1A-NO)") (class "Default")
      (node (ref "R8") (pin "2") (pinfunction "2_2") (pintype "passive"))
      (node (ref "U$1") (pin "2") (pinfunction "NO_2") (pintype "passive"))
    )
    (net (code "42") (name "Net-(U$1B-NC)") (class "Default")
      (node (ref "R11") (pin "2") (pinfunction "2_2") (pintype "passive"))
      (node (ref "U$1") (pin "7") (pinfunction "NC_7") (pintype "passive"))
    )
    (net (code "43") (name "Net-(U$1B-NO)") (class "Default")
      (node (ref "R4") (pin "2") (pinfunction "2_2") (pintype "passive"))
      (node (ref "U$1") (pin "4") (pinfunction "NO_4") (pintype "passive"))
    )
    (net (code "44") (name "Net-(U$2A--IN)") (class "Default")
      (node (ref "R5") (pin "2") (pinfunction "2_2") (pintype "passive"))
      (node (ref "U$2") (pin "1") (pinfunction "OUT_1") (pintype "output"))
      (node (ref "U$2") (pin "4") (pinfunction "-IN_4") (pintype "input"))
    )
    (net (code "45") (name "Net-(U$4-BP)") (class "Default")
      (node (ref "C7") (pin "1") (pinfunction "1_1") (pintype "passive"))
      (node (ref "U$4") (pin "4") (pinfunction "BP_4") (pintype "bidirectional"))
    )
    (net (code "46") (name "Net-(U$4-EN)") (class "Default")
      (node (ref "R14") (pin "1") (pinfunction "1_1") (pintype "passive"))
      (node (ref "U$4") (pin "3") (pinfunction "EN_3") (pintype "bidirectional"))
    )
    (net (code "47") (name "Net-(U$5-1)") (class "Default")
      (node (ref "R17") (pin "2") (pinfunction "2_2") (pintype "passive"))
      (node (ref "U$5") (pin "P$1") (pinfunction "1_P$1") (pintype "passive"))
    )
    (net (code "48") (name "Net-(U$6-GRID1)") (class "Default")
      (node (ref "U$6") (pin "12") (pinfunction "GRID1_12") (pintype "bidirectional"))
      (node (ref "U$8") (pin "P18") (pinfunction "GRID1_P18") (pintype "bidirectional"))
    )
    (net (code "49") (name "Net-(U$6-GRID2)") (class "Default")
      (node (ref "U$6") (pin "9") (pinfunction "GRID2_9") (pintype "bidirectional"))
      (node (ref "U$8") (pin "P17") (pinfunction "GRID2_P17") (pintype "bidirectional"))
    )
    (net (code "50") (name "Net-(U$6-GRID3)") (class "Default")
      (node (ref "U$6") (pin "8") (pinfunction "GRID3_8") (pintype "bidirectional"))
      (node (ref "U$8") (pin "P15") (pinfunction "GRID3_P15") (pintype "bidirectional"))
    )
    (net (code "51") (name "Net-(U$6-GRID4)") (class "Default")
      (node (ref "U$6") (pin "6") (pinfunction "GRID4_6") (pintype "bidirectional"))
      (node (ref "U$8") (pin "P14") (pinfunction "GRID4_P14") (pintype "bidirectional"))
    )
    (net (code "52") (name "Net-(U$6-SEG_A)") (class "Default")
      (node (ref "U$6") (pin "11") (pinfunction "SEG_A_11") (pintype "bidirectional"))
      (node (ref "U$8") (pin "P6") (pinfunction "SEG1_P6") (pintype "bidirectional"))
    )
    (net (code "53") (name "Net-(U$6-SEG_B)") (class "Default")
      (node (ref "U$6") (pin "7") (pinfunction "SEG_B_7") (pintype "bidirectional"))
      (node (ref "U$8") (pin "P7") (pinfunction "SEG2_P7") (pintype "bidirectional"))
    )
    (net (code "54") (name "Net-(U$6-SEG_C)") (class "Default")
      (node (ref "U$6") (pin "4") (pinfunction "SEG_C_4") (pintype "bidirectional"))
      (node (ref "U$8") (pin "P8") (pinfunction "SEG3_P8") (pintype "bidirectional"))
    )
    (net (code "55") (name "Net-(U$6-SEG_D)") (class "Default")
      (node (ref "U$6") (pin "2") (pinfunction "SEG_D_2") (pintype "bidirectional"))
      (node (ref "U$8") (pin "P9") (pinfunction "SEG4_P9") (pintype "bidirectional"))
    )
    (net (code "56") (name "Net-(U$6-SEG_DP)") (class "Default")
      (node (ref "U$6") (pin "3") (pinfunction "SEG_DP_3") (pintype "bidirectional"))
      (node (ref "U$8") (pin "P13") (pinfunction "SEG14_P13") (pintype "bidirectional"))
    )
    (net (code "57") (name "Net-(U$6-SEG_E)") (class "Default")
      (node (ref "U$6") (pin "1") (pinfunction "SEG_E_1") (pintype "bidirectional"))
      (node (ref "U$8") (pin "P10") (pinfunction "SEG5_P10") (pintype "bidirectional"))
    )
    (net (code "58") (name "Net-(U$6-SEG_F)") (class "Default")
      (node (ref "U$6") (pin "10") (pinfunction "SEG_F_10") (pintype "bidirectional"))
      (node (ref "U$8") (pin "P11") (pinfunction "SEG12_P11") (pintype "bidirectional"))
    )
    (net (code "59") (name "Net-(U$6-SEG_G)") (class "Default")
      (node (ref "U$6") (pin "5") (pinfunction "SEG_G_5") (pintype "bidirectional"))
      (node (ref "U$8") (pin "P12") (pinfunction "SEG13_P12") (pintype "bidirectional"))
    )
    (net (code "60") (name "Net-(U$7-IN+)") (class "Default")
      (node (ref "R26") (pin "2") (pinfunction "2_2") (pintype "passive"))
      (node (ref "U$7") (pin "4") (pinfunction "IN+_4") (pintype "bidirectional"))
    )
    (net (code "61") (name "Net-(U$7-OUT)") (class "Default")
      (node (ref "U$7") (pin "6") (pinfunction "OUT_6") (pintype "bidirectional"))
      (node (ref "U2") (pin "4") (pinfunction "AIN0_4") (pintype "input"))
    )
    (net (code "62") (name "Net-(U$9-BOOT0)") (class "Default")
      (node (ref "R15") (pin "2") (pinfunction "2_2") (pintype "passive"))
      (node (ref "U$9") (pin "44") (pinfunction "BOOT0_44") (pintype "input"))
    )
    (net (code "63") (name "Net-(U2-AIN2)") (class "Default")
      (node (ref "C5") (pin "1") (pinfunction "1_1") (pintype "passive"))
      (node (ref "R5") (pin "1") (pinfunction "1_1") (pintype "passive"))
      (node (ref "U2") (pin "6") (pinfunction "AIN2_6") (pintype "input"))
    )
    (net (code "64") (name "OSC_IN") (class "Default")
      (node (ref "C9") (pin "2") (pinfunction "2_2") (pintype "passive"))
      (node (ref "U$9") (pin "5") (pinfunction "PD0-OSC_IN_5") (pintype "input"))
      (node (ref "Y1") (pin "P$2") (pinfunction "2_P$2") (pintype "passive"))
    )
    (net (code "65") (name "OSC_OUT") (class "Default")
      (node (ref "C12") (pin "2") (pinfunction "2_2") (pintype "passive"))
      (node (ref "U$9") (pin "6") (pinfunction "PD1-OSC_OUT_6") (pintype "input"))
      (node (ref "Y1") (pin "P$1") (pinfunction "1_P$1") (pintype "passive"))
    )
    (net (code "66") (name "RESET") (class "Default")
      (node (ref "R16") (pin "1") (pinfunction "1_1") (pintype "passive"))
      (node (ref "U$5") (pin "P$2") (pinfunction "2_P$2") (pintype "passive"))
      (node (ref "U$9") (pin "7") (pinfunction "NRST_7") (pintype "input"))
    )
    (net (code "67") (name "RES_ENA") (class "Default")
      (node (ref "Q6") (pin "1") (pinfunction "G_1") (pintype "passive"))
      (node (ref "R9") (pin "2") (pinfunction "2_2") (pintype "passive"))
      (node (ref "S1") (pin "2") (pinfunction "2_2") (pintype "passive"))
      (node (ref "U$3") (pin "2") (pinfunction "A_2") (pintype "input"))
      (node (ref "U$9") (pin "26") (pinfunction "PB13/SPI2_SCK/USART3_CTS/TIM1_CH1N_26") (pintype "input"))
    )
    (net (code "68") (name "RES_RANGE") (class "Default")
      (node (ref "U$1") (pin "5") (pinfunction "IN_5") (pintype "input"))
      (node (ref "U$9") (pin "20") (pinfunction "PB2/BOOT1_20") (pintype "bidirectional"))
    )
    (net (code "69") (name "SCLK") (class "Default")
      (node (ref "U$8") (pin "P2") (pinfunction "SCLK_P2") (pintype "bidirectional"))
      (node (ref "U$9") (pin "15") (pinfunction "PA5/SPI1_SCK/ADC12_IN5_15") (pintype "bidirectional"))
      (node (ref "U2") (pin "1") (pinfunction "SCLK_1") (pintype "input"))
    )
    (net (code "70") (name "SS_ADC") (class "Default")
      (node (ref "U$9") (pin "18") (pinfunction "PB0/ADC12_IN8/TIM3_CH3_18") (pintype "bidirectional"))
      (node (ref "U2") (pin "2") (pinfunction "CS_2") (pintype "input"))
    )
    (net (code "71") (name "SS_LED") (class "Default")
      (node (ref "U$8") (pin "P3") (pinfunction "CS_P3") (pintype "bidirectional"))
      (node (ref "U$9") (pin "14") (pinfunction "PA4/SPI1_NSS/USART2_CK/ADC12_IN4_14") (pintype "bidirectional"))
    )
    (net (code "72") (name "SWCLK") (class "Default")
      (node (ref "SWD") (pin "2") (pinfunction "2_2") (pintype "passive"))
      (node (ref "U$9") (pin "37") (pinfunction "PA14/JTCK/SWCLK_37") (pintype "bidirectional"))
    )
    (net (code "73") (name "SWDIO") (class "Default")
      (node (ref "SWD") (pin "3") (pinfunction "3_3") (pintype "passive"))
      (node (ref "U$9") (pin "34") (pinfunction "PA13/JTMS/SWDIO_34") (pintype "bidirectional"))
    )
    (net (code "74") (name "USBDM") (class "Default")
      (node (ref "C10") (pin "2") (pinfunction "2_2") (pintype "passive"))
      (node (ref "R6") (pin "1") (pinfunction "1_1") (pintype "passive"))
      (node (ref "U$9") (pin "32") (pinfunction "PA11/USART1_CTS/CAN_RX/TIM1_CH4/USBDM_32") (pintype "bidirectional"))
    )
    (net (code "75") (name "USBDP") (class "Default")
      (node (ref "C11") (pin "2") (pinfunction "2_2") (pintype "passive"))
      (node (ref "R19") (pin "1") (pinfunction "1_1") (pintype "passive"))
      (node (ref "R7") (pin "1") (pinfunction "1_1") (pintype "passive"))
      (node (ref "U$9") (pin "33") (pinfunction "PA12/USART1_RTS/CAN_TX/TIM1_ETR/USBDP_33") (pintype "bidirectional"))
    )
    (net (code "76") (name "VBAT") (class "Default")
      (node (ref "U$9") (pin "1") (pinfunction "VBAT_1") (pintype "power_in"))
    )
    (net (code "77") (name "VOLT_ENA") (class "Default")
      (node (ref "R24") (pin "2") (pinfunction "2_2") (pintype "passive"))
      (node (ref "S1") (pin "1") (pinfunction "1_1") (pintype "passive"))
      (node (ref "U$9") (pin "27") (pinfunction "PB14/SPI2_MISO/USART3_RTS/TIM1_CH2N_27") (pintype "input"))
    )
    (net (code "78") (name "VOLT_RANGE") (class "Default")
      (node (ref "U$1") (pin "1") (pinfunction "IN_1") (pintype "input"))
      (node (ref "U$9") (pin "21") (pinfunction "PB10/I2C2_SCL/USART3_TX_21") (pintype "input"))
    )
    (net (code "79") (name "unconnected-(U$7-REF-Pad1)") (class "Default")
      (node (ref "U$7") (pin "1") (pinfunction "REF_1") (pintype "bidirectional"))
    )
    (net (code "80") (name "unconnected-(U$8-K2-PadP4)") (class "Default")
      (node (ref "U$8") (pin "P4") (pinfunction "K2_P4") (pintype "bidirectional"))
    )
    (net (code "81") (name "unconnected-(U$9-PA0_WKUP{slash}USART2_CTS{slash}ADC12_IN0{slash}TIM2_CH1_ETR-Pad10)") (class "Default")
      (node (ref "U$9") (pin "10") (pinfunction "PA0_WKUP/USART2_CTS/ADC12_IN0/TIM2_CH1_ETR_10") (pintype "bidirectional"))
    )
    (net (code "82") (name "unconnected-(U$9-PA1{slash}USART2_RTS{slash}ADC12_IN1{slash}TIM2_CH2-Pad11)") (class "Default")
      (node (ref "U$9") (pin "11") (pinfunction "PA1/USART2_RTS/ADC12_IN1/TIM2_CH2_11") (pintype "bidirectional"))
    )
    (net (code "83") (name "unconnected-(U$9-PA8{slash}USART1_CK{slash}TIM1_CH1{slash}MCO-Pad29)") (class "Default")
      (node (ref "U$9") (pin "29") (pinfunction "PA8/USART1_CK/TIM1_CH1/MCO_29") (pintype "bidirectional"))
    )
    (net (code "84") (name "unconnected-(U$9-PB8{slash}TIM4_CH3-Pad45)") (class "Default")
      (node (ref "U$9") (pin "45") (pinfunction "PB8/TIM4_CH3_45") (pintype "bidirectional"))
    )
    (net (code "85") (name "unconnected-(U$9-PB11{slash}I2C2_SDA{slash}USART3_RX-Pad22)") (class "Default")
      (node (ref "U$9") (pin "22") (pinfunction "PB11/I2C2_SDA/USART3_RX_22") (pintype "input"))
    )
    (net (code "86") (name "unconnected-(U$9-PB15{slash}SPI2_MOSI{slash}TIM1_CH3N-Pad28)") (class "Default")
      (node (ref "U$9") (pin "28") (pinfunction "PB15/SPI2_MOSI/TIM1_CH3N_28") (pintype "input"))
    )
    (net (code "87") (name "unconnected-(U$9-PC13-TAMPER-RTC-Pad2)") (class "Default")
      (node (ref "U$9") (pin "2") (pinfunction "PC13-TAMPER-RTC_2") (pintype "input"))
    )
    (net (code "88") (name "unconnected-(U$9-PC14-OSC32_IN-Pad3)") (class "Default")
      (node (ref "U$9") (pin "3") (pinfunction "PC14-OSC32_IN_3") (pintype "input"))
    )
    (net (code "89") (name "unconnected-(U$9-PC15-OSC32_OUT-Pad4)") (class "Default")
      (node (ref "U$9") (pin "4") (pinfunction "PC15-OSC32_OUT_4") (pintype "input"))
    )
    (net (code "90") (name "unconnected-(X1-PadID)") (class "Default")
      (node (ref "X1") (pin "ID") (pinfunction "ID_ID") (pintype "bidirectional"))
    )
  )
)
